# control.net
KiCad netlist of a schematic drawn in Altium Designer
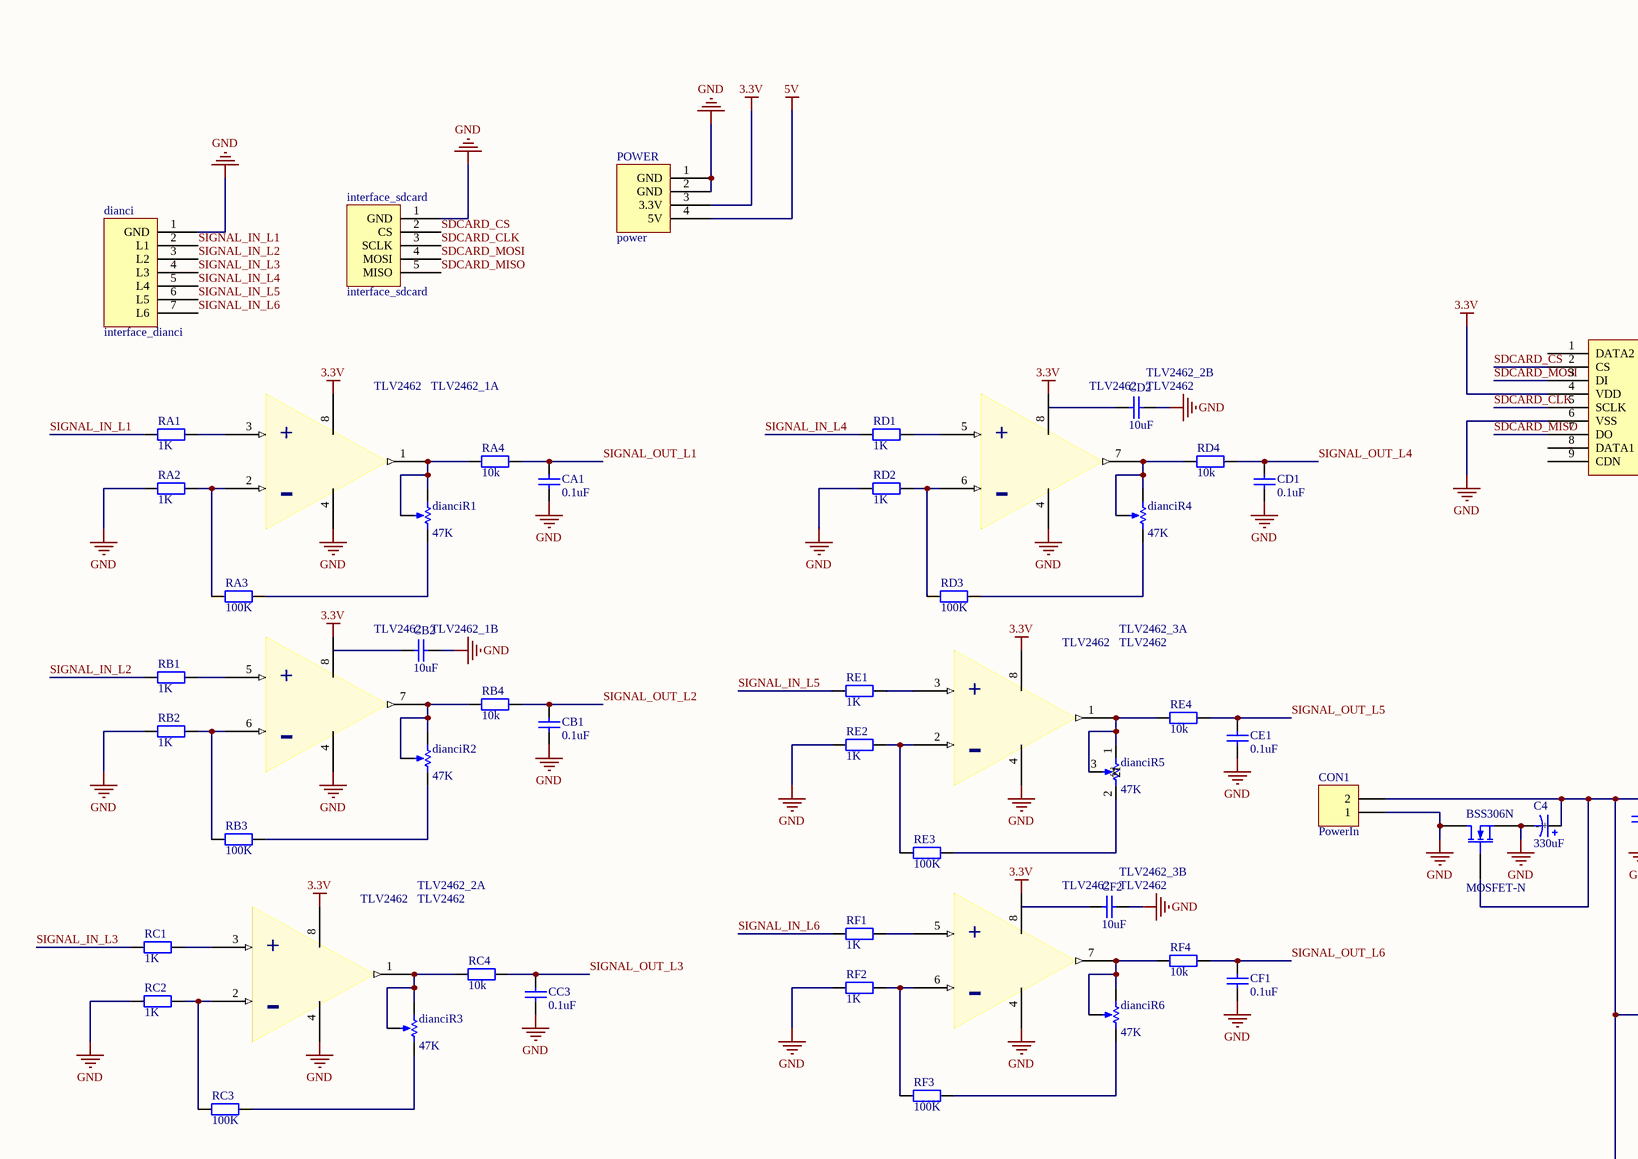
[diagram p0: control.SchDoc, top left]
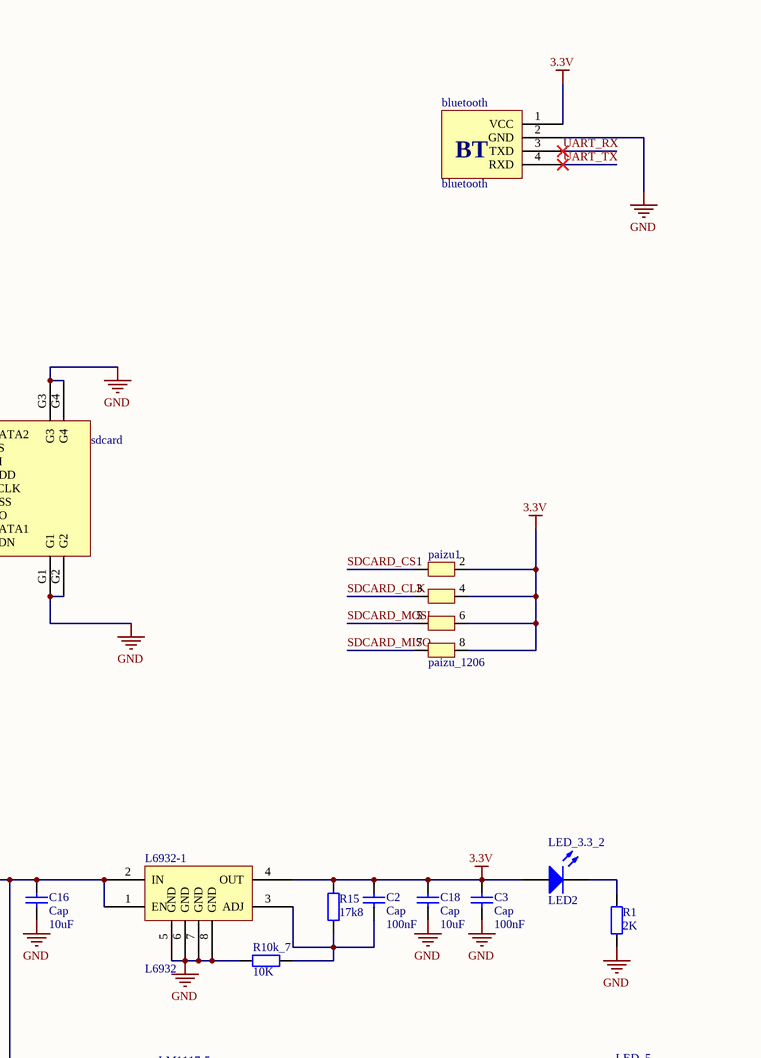
[diagram p1: control.SchDoc, top right]
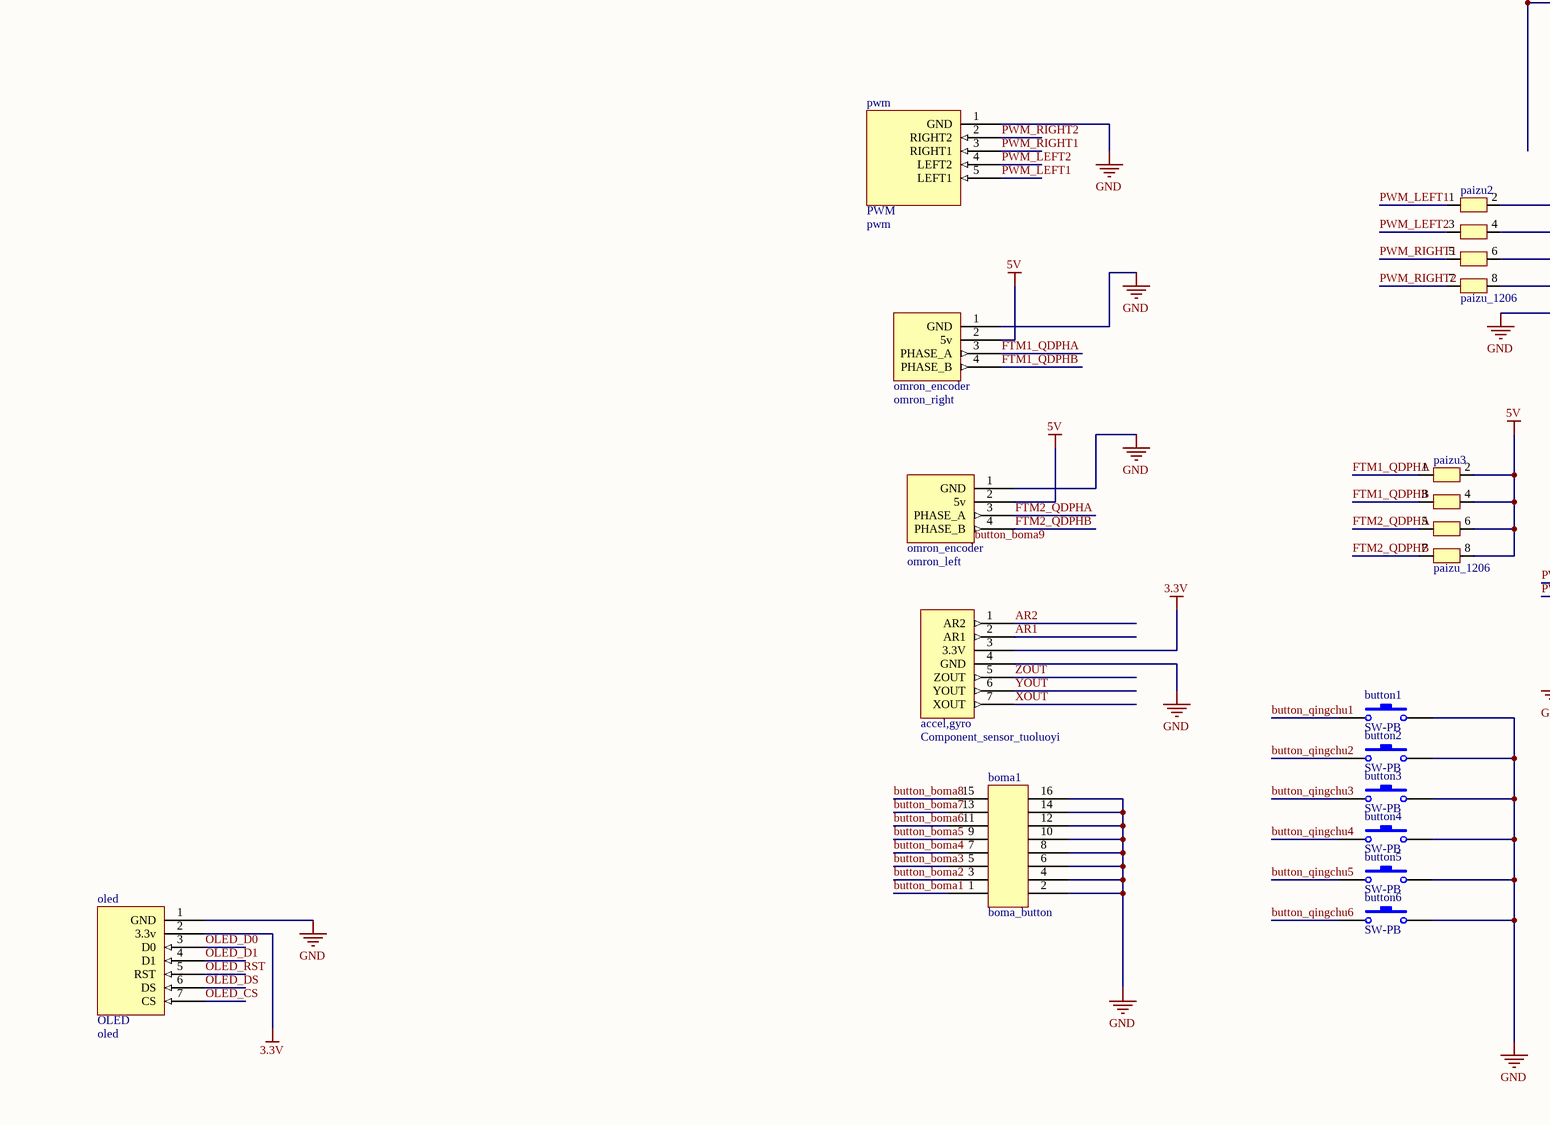
[diagram p2: control.SchDoc, bottom left]
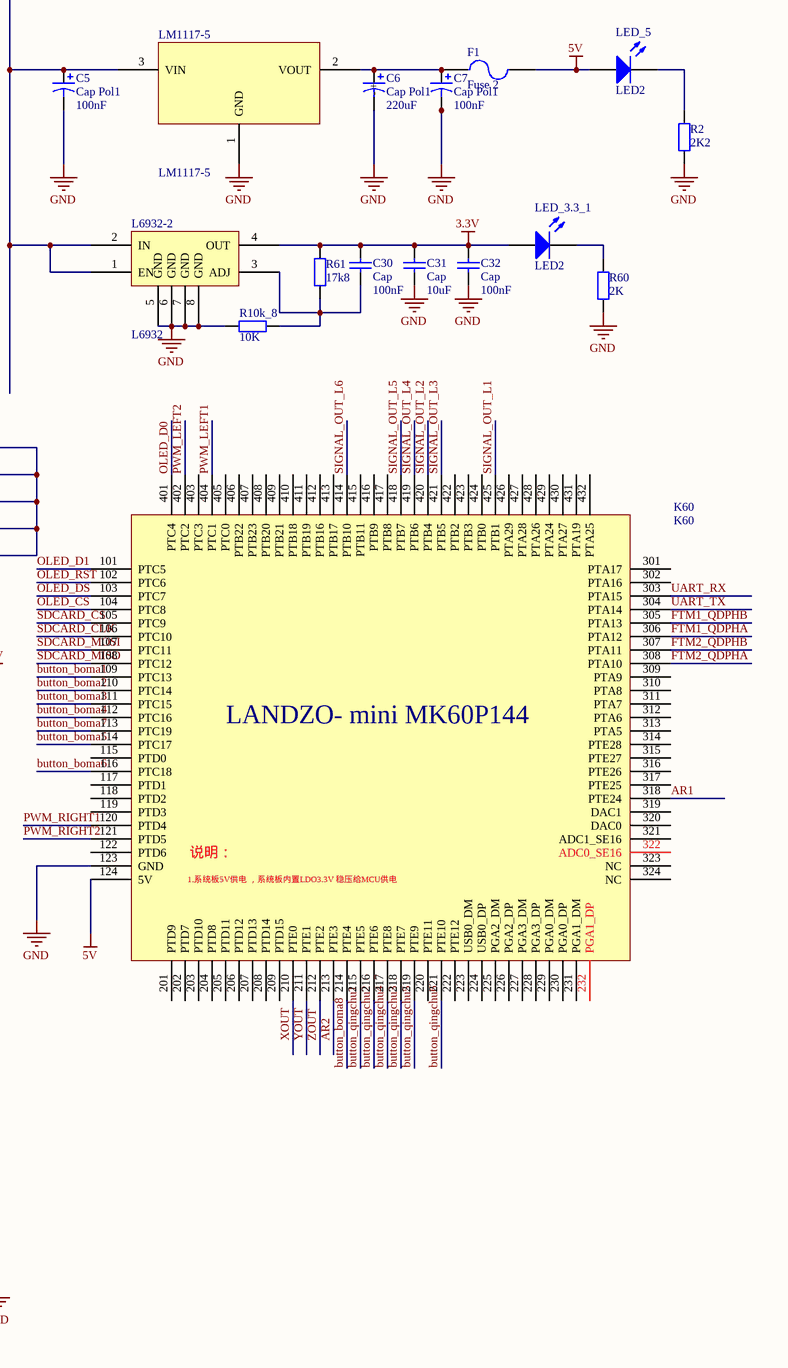
[diagram p3: control.SchDoc, bottom right]

(export (version "E")
  (design (tool "Eeschema 10.0.6"))
  (components
    (comp (ref "bluetooth")
      (value "bluetooth")
      (footprint "HDR1X4")
      (libsource (lib "PCB_Project1") (part "bluetooth"))
    )
    (comp (ref "boma1")
      (value "boma_button")
      (footprint "config_8")
      (libsource (lib "Schlib_k60_core") (part "boma_button"))
    )
    (comp (ref "BSS306N")
      (value "MOSFET-N")
      (footprint "SOT-23_M")
      (description "N-Channel MOSFET")
      (fields (field (name "PUBLISHER") "Altium Limited"))
      (libsource (lib "Miscellaneous Devices") (part "MOSFET-N"))
    )
    (comp (ref "button1")
      (value "SW-PB")
      (footprint "button")
      (description "Switch")
      (fields (field (name "PUBLISHER") "Altium Limited"))
      (libsource (lib "Miscellaneous Devices") (part "SW-PB"))
    )
    (comp (ref "button2")
      (value "SW-PB")
      (footprint "button")
      (description "Switch")
      (fields (field (name "PUBLISHER") "Altium Limited"))
      (libsource (lib "Miscellaneous Devices") (part "SW-PB"))
    )
    (comp (ref "button3")
      (value "SW-PB")
      (footprint "button")
      (description "Switch")
      (fields (field (name "PUBLISHER") "Altium Limited"))
      (libsource (lib "Miscellaneous Devices") (part "SW-PB"))
    )
    (comp (ref "button4")
      (value "SW-PB")
      (footprint "button")
      (description "Switch")
      (fields (field (name "PUBLISHER") "Altium Limited"))
      (libsource (lib "Miscellaneous Devices") (part "SW-PB"))
    )
    (comp (ref "button5")
      (value "SW-PB")
      (footprint "button")
      (description "Switch")
      (fields (field (name "PUBLISHER") "Altium Limited"))
      (libsource (lib "Miscellaneous Devices") (part "SW-PB"))
    )
    (comp (ref "button6")
      (value "SW-PB")
      (footprint "button")
      (description "Switch")
      (fields (field (name "PUBLISHER") "Altium Limited"))
      (libsource (lib "Miscellaneous Devices") (part "SW-PB"))
    )
    (comp (ref "C2")
      (value "Cap")
      (footprint "0805")
      (description "Capacitor")
      (fields (field (name "ALTIUM_VALUE") "100nF") (field (name "PUBLISHER") "Altium Limited"))
      (libsource (lib "Miscellaneous Devices") (part "Cap"))
    )
    (comp (ref "C3")
      (value "Cap")
      (footprint "0805")
      (description "Capacitor")
      (fields (field (name "ALTIUM_VALUE") "100nF") (field (name "PUBLISHER") "Altium Limited"))
      (libsource (lib "Miscellaneous Devices") (part "Cap"))
    )
    (comp (ref "C4")
      (value "330uF")
      (footprint "RB5-10.5")
      (description "Polarized Capacitor (Radial)")
      (fields (field (name "Comment") "Cap Pol1") (field (name "PUBLISHER") "Altium Limited"))
      (libsource (lib "Miscellaneous Devices") (part "Cap Pol1"))
    )
    (comp (ref "C5")
      (value "Cap Pol1")
      (footprint "钽电容_小")
      (description "Polarized Capacitor (Radial)")
      (fields (field (name "ALTIUM_VALUE") "100nF") (field (name "PUBLISHER") "Altium Limited"))
      (libsource (lib "") (part "Cap Pol1_1"))
    )
    (comp (ref "C6")
      (value "Cap Pol1")
      (footprint "D7343")
      (description "Polarized Capacitor (Radial)")
      (fields (field (name "ALTIUM_VALUE") "220uF") (field (name "PUBLISHER") "Altium Limited"))
      (libsource (lib "Miscellaneous Devices") (part "Cap Pol1"))
    )
    (comp (ref "C7")
      (value "Cap Pol1")
      (footprint "钽电容_小")
      (description "Polarized Capacitor (Radial)")
      (fields (field (name "ALTIUM_VALUE") "100nF") (field (name "PUBLISHER") "Altium Limited"))
      (libsource (lib "") (part "Cap Pol1_1"))
    )
    (comp (ref "C16")
      (value "Cap")
      (footprint "0805")
      (description "Capacitor")
      (fields (field (name "ALTIUM_VALUE") "10uF") (field (name "PUBLISHER") "Altium Limited"))
      (libsource (lib "Miscellaneous Devices") (part "Cap"))
    )
    (comp (ref "C18")
      (value "Cap")
      (footprint "0805")
      (description "Capacitor")
      (fields (field (name "ALTIUM_VALUE") "10uF") (field (name "PUBLISHER") "Altium Limited"))
      (libsource (lib "Miscellaneous Devices") (part "Cap"))
    )
    (comp (ref "C30")
      (value "Cap")
      (footprint "0805")
      (description "Capacitor")
      (fields (field (name "ALTIUM_VALUE") "100nF") (field (name "PUBLISHER") "Altium Limited"))
      (libsource (lib "Miscellaneous Devices") (part "Cap"))
    )
    (comp (ref "C31")
      (value "Cap")
      (footprint "0805")
      (description "Capacitor")
      (fields (field (name "ALTIUM_VALUE") "10uF") (field (name "PUBLISHER") "Altium Limited"))
      (libsource (lib "Miscellaneous Devices") (part "Cap"))
    )
    (comp (ref "C32")
      (value "Cap")
      (footprint "0805")
      (description "Capacitor")
      (fields (field (name "ALTIUM_VALUE") "100nF") (field (name "PUBLISHER") "Altium Limited"))
      (libsource (lib "Miscellaneous Devices") (part "Cap"))
    )
    (comp (ref "CA1")
      (value "0.1uF")
      (footprint "0805")
      (description "Capacitor")
      (fields (field (name "Comment") "Cap") (field (name "PUBLISHER") "Altium Limited"))
      (libsource (lib "Miscellaneous Devices") (part "Cap"))
    )
    (comp (ref "CB1")
      (value "0.1uF")
      (footprint "0805")
      (description "Capacitor")
      (fields (field (name "Comment") "Cap") (field (name "PUBLISHER") "Altium Limited"))
      (libsource (lib "Miscellaneous Devices") (part "Cap"))
    )
    (comp (ref "CB2")
      (value "10uF")
      (footprint "0805")
      (description "Capacitor")
      (fields (field (name "Comment") "Cap") (field (name "PUBLISHER") "Altium Limited"))
      (libsource (lib "Miscellaneous Devices") (part "Cap"))
    )
    (comp (ref "CC3")
      (value "0.1uF")
      (footprint "0805")
      (description "Capacitor")
      (fields (field (name "Comment") "Cap") (field (name "PUBLISHER") "Altium Limited"))
      (libsource (lib "Miscellaneous Devices") (part "Cap"))
    )
    (comp (ref "CD1")
      (value "0.1uF")
      (footprint "0805")
      (description "Capacitor")
      (fields (field (name "Comment") "Cap") (field (name "PUBLISHER") "Altium Limited"))
      (libsource (lib "Miscellaneous Devices") (part "Cap"))
    )
    (comp (ref "CD2")
      (value "10uF")
      (footprint "0805")
      (description "Capacitor")
      (fields (field (name "Comment") "Cap") (field (name "PUBLISHER") "Altium Limited"))
      (libsource (lib "Miscellaneous Devices") (part "Cap"))
    )
    (comp (ref "CE1")
      (value "0.1uF")
      (footprint "0805")
      (description "Capacitor")
      (fields (field (name "Comment") "Cap") (field (name "PUBLISHER") "Altium Limited"))
      (libsource (lib "Miscellaneous Devices") (part "Cap"))
    )
    (comp (ref "CF1")
      (value "0.1uF")
      (footprint "0805")
      (description "Capacitor")
      (fields (field (name "Comment") "Cap") (field (name "PUBLISHER") "Altium Limited"))
      (libsource (lib "Miscellaneous Devices") (part "Cap"))
    )
    (comp (ref "CF2")
      (value "10uF")
      (footprint "0805")
      (description "Capacitor")
      (fields (field (name "Comment") "Cap") (field (name "PUBLISHER") "Altium Limited"))
      (libsource (lib "Miscellaneous Devices") (part "Cap"))
    )
    (comp (ref "CON1")
      (value "PowerIn")
      (footprint "接线端子")
      (description "Header, 2-Pin")
      (fields (field (name "PUBLISHER") "Altium Limited"))
      (libsource (lib "Miscellaneous Connectors") (part "Header 2"))
    )
    (comp (ref "dianci")
      (value "interface_dianci")
      (footprint "HDR1X7H")
      (libsource (lib "Schlib_k60_core") (part "interface_dianci"))
    )
    (comp (ref "dianciR1")
      (value "47K")
      (footprint "滑动变阻器")
      (description "Potentiometer")
      (fields (field (name "Comment") "R4") (field (name "PUBLISHER") "Altium Limited"))
      (libsource (lib "") (part "RPot_1"))
    )
    (comp (ref "dianciR2")
      (value "47K")
      (footprint "滑动变阻器")
      (description "Potentiometer")
      (fields (field (name "Comment") "R4") (field (name "PUBLISHER") "Altium Limited"))
      (libsource (lib "") (part "RPot_1"))
    )
    (comp (ref "dianciR3")
      (value "47K")
      (footprint "滑动变阻器")
      (description "Potentiometer")
      (fields (field (name "Comment") "R4") (field (name "PUBLISHER") "Altium Limited"))
      (libsource (lib "") (part "RPot_1"))
    )
    (comp (ref "dianciR4")
      (value "47K")
      (footprint "滑动变阻器")
      (description "Potentiometer")
      (fields (field (name "Comment") "R4") (field (name "PUBLISHER") "Altium Limited"))
      (libsource (lib "") (part "RPot_1"))
    )
    (comp (ref "dianciR5")
      (value "47K")
      (footprint "滑动变阻器")
      (description "Potentiometer")
      (fields (field (name "Comment") "R4") (field (name "PUBLISHER") "Altium Limited"))
      (libsource (lib "Miscellaneous Devices") (part "RPot"))
    )
    (comp (ref "dianciR6")
      (value "47K")
      (footprint "滑动变阻器")
      (description "Potentiometer")
      (fields (field (name "Comment") "R4") (field (name "PUBLISHER") "Altium Limited"))
      (libsource (lib "") (part "RPot_1"))
    )
    (comp (ref "F1")
      (value "Fuse 2")
      (footprint "0805")
      (description "Fuse")
      (fields (field (name "PUBLISHER") "Altium Limited"))
      (libsource (lib "Miscellaneous Devices") (part "Fuse 2"))
    )
    (comp (ref "interface_sdcard")
      (value "interface_sdcard")
      (footprint "HDR1X5H")
      (libsource (lib "Schlib_k60_core") (part "interface_sdcard"))
    )
    (comp (ref "K60")
      (value "K60")
      (footprint "K60 V4.0最小系统版")
      (libsource (lib "K60P144 V5.1") (part "Component_1"))
    )
    (comp (ref "L6932-1")
      (value "L6932")
      (footprint "L6932")
      (libsource (lib "Schlib_k60_core") (part "L6932"))
    )
    (comp (ref "L6932-2")
      (value "L6932")
      (footprint "L6932")
      (libsource (lib "Schlib_k60_core") (part "L6932"))
    )
    (comp (ref "LED_3.3_1")
      (value "LED2")
      (footprint "0805")
      (description "Typical RED, GREEN, YELLOW, AMBER GaAs LED")
      (fields (field (name "PUBLISHER") "Altium Limited"))
      (libsource (lib "Miscellaneous Devices") (part "LED2"))
    )
    (comp (ref "LED_3.3_2")
      (value "LED2")
      (footprint "0805")
      (description "Typical RED, GREEN, YELLOW, AMBER GaAs LED")
      (fields (field (name "PUBLISHER") "Altium Limited"))
      (libsource (lib "Miscellaneous Devices") (part "LED2"))
    )
    (comp (ref "LED_5")
      (value "LED2")
      (footprint "0805")
      (description "Typical RED, GREEN, YELLOW, AMBER GaAs LED")
      (fields (field (name "PUBLISHER") "Altium Limited"))
      (libsource (lib "Miscellaneous Devices") (part "LED2"))
    )
    (comp (ref "LM1117-5")
      (value "LM1117-5")
      (footprint "SOT223_M")
      (libsource (lib "Schlib_k60_core") (part "LM1117-5"))
    )
    (comp (ref "oled") (value "oled") (footprint "HDR1X7H") (libsource (lib "Schlib_k60_core") (part "oled")))
    (comp (ref "omron_left")
      (value "omron_encoder")
      (footprint "HDR1X4H")
      (libsource (lib "Schlib_k60_core") (part "omron_encoder"))
    )
    (comp (ref "omron_right")
      (value "omron_encoder")
      (footprint "HDR1X4H")
      (libsource (lib "Schlib_k60_core") (part "omron_encoder"))
    )
    (comp (ref "paizu1")
      (value "paizu_1206")
      (footprint "paizu")
      (libsource (lib "Schlib_k60_core") (part "paizu_1206"))
    )
    (comp (ref "paizu2")
      (value "paizu_1206")
      (footprint "paizu")
      (libsource (lib "Schlib_k60_core") (part "paizu_1206"))
    )
    (comp (ref "paizu3")
      (value "paizu_1206")
      (footprint "paizu")
      (libsource (lib "Schlib_k60_core") (part "paizu_1206"))
    )
    (comp (ref "POWER")
      (value "power")
      (footprint "HDR1X4H")
      (libsource (lib "Schlib_k60_core") (part "power"))
    )
    (comp (ref "pwm") (value "pwm") (footprint "HDR1X5H") (libsource (lib "Schlib_k60_core") (part "pwm")))
    (comp (ref "R1")
      (value "2K")
      (footprint "0805")
      (description "Resistor")
      (fields (field (name "Comment") "Res2") (field (name "PUBLISHER") "Altium Limited"))
      (libsource (lib "Miscellaneous Devices") (part "Res2"))
    )
    (comp (ref "R2")
      (value "2K2")
      (footprint "0805")
      (description "Resistor")
      (fields (field (name "Comment") "Res2") (field (name "PUBLISHER") "Altium Limited"))
      (libsource (lib "Miscellaneous Devices") (part "Res2"))
    )
    (comp (ref "R10k_7")
      (value "10K")
      (footprint "0805")
      (description "Resistor")
      (fields (field (name "Comment") "Res2") (field (name "PUBLISHER") "Altium Limited"))
      (libsource (lib "") (part "Res2_1"))
    )
    (comp (ref "R10k_8")
      (value "10K")
      (footprint "0805")
      (description "Resistor")
      (fields (field (name "Comment") "Res2") (field (name "PUBLISHER") "Altium Limited"))
      (libsource (lib "") (part "Res2_1"))
    )
    (comp (ref "R15")
      (value "17k8")
      (footprint "0805")
      (description "Resistor")
      (fields (field (name "Comment") "Res2") (field (name "PUBLISHER") "Altium Limited"))
      (libsource (lib "Miscellaneous Devices") (part "Res2"))
    )
    (comp (ref "R60")
      (value "2K")
      (footprint "0805")
      (description "Resistor")
      (fields (field (name "Comment") "Res2") (field (name "PUBLISHER") "Altium Limited"))
      (libsource (lib "Miscellaneous Devices") (part "Res2"))
    )
    (comp (ref "R61")
      (value "17k8")
      (footprint "0805")
      (description "Resistor")
      (fields (field (name "Comment") "Res2") (field (name "PUBLISHER") "Altium Limited"))
      (libsource (lib "Miscellaneous Devices") (part "Res2"))
    )
    (comp (ref "RA1")
      (value "1K")
      (footprint "0805")
      (description "Resistor")
      (fields (field (name "Comment") "Res2") (field (name "PUBLISHER") "Altium Limited"))
      (libsource (lib "") (part "Res2_1"))
    )
    (comp (ref "RA2")
      (value "1K")
      (footprint "0805")
      (description "Resistor")
      (fields (field (name "Comment") "Res2") (field (name "PUBLISHER") "Altium Limited"))
      (libsource (lib "") (part "Res2_1"))
    )
    (comp (ref "RA3")
      (value "100K")
      (footprint "0805")
      (description "Resistor")
      (fields (field (name "Comment") "Res2") (field (name "PUBLISHER") "Altium Limited"))
      (libsource (lib "") (part "Res2_1"))
    )
    (comp (ref "RA4")
      (value "10k")
      (footprint "0805")
      (description "Resistor")
      (fields (field (name "Comment") "Res2") (field (name "PUBLISHER") "Altium Limited"))
      (libsource (lib "") (part "Res2_1"))
    )
    (comp (ref "RB1")
      (value "1K")
      (footprint "0805")
      (description "Resistor")
      (fields (field (name "Comment") "Res2") (field (name "PUBLISHER") "Altium Limited"))
      (libsource (lib "") (part "Res2_1"))
    )
    (comp (ref "RB2")
      (value "1K")
      (footprint "0805")
      (description "Resistor")
      (fields (field (name "Comment") "Res2") (field (name "PUBLISHER") "Altium Limited"))
      (libsource (lib "") (part "Res2_1"))
    )
    (comp (ref "RB3")
      (value "100K")
      (footprint "0805")
      (description "Resistor")
      (fields (field (name "Comment") "Res2") (field (name "PUBLISHER") "Altium Limited"))
      (libsource (lib "") (part "Res2_1"))
    )
    (comp (ref "RB4")
      (value "10k")
      (footprint "0805")
      (description "Resistor")
      (fields (field (name "Comment") "Res2") (field (name "PUBLISHER") "Altium Limited"))
      (libsource (lib "") (part "Res2_1"))
    )
    (comp (ref "RC1")
      (value "1K")
      (footprint "0805")
      (description "Resistor")
      (fields (field (name "Comment") "Res2") (field (name "PUBLISHER") "Altium Limited"))
      (libsource (lib "") (part "Res2_1"))
    )
    (comp (ref "RC2")
      (value "1K")
      (footprint "0805")
      (description "Resistor")
      (fields (field (name "Comment") "Res2") (field (name "PUBLISHER") "Altium Limited"))
      (libsource (lib "") (part "Res2_1"))
    )
    (comp (ref "RC3")
      (value "100K")
      (footprint "0805")
      (description "Resistor")
      (fields (field (name "Comment") "Res2") (field (name "PUBLISHER") "Altium Limited"))
      (libsource (lib "") (part "Res2_1"))
    )
    (comp (ref "RC4")
      (value "10k")
      (footprint "0805")
      (description "Resistor")
      (fields (field (name "Comment") "Res2") (field (name "PUBLISHER") "Altium Limited"))
      (libsource (lib "") (part "Res2_1"))
    )
    (comp (ref "RD1")
      (value "1K")
      (footprint "0805")
      (description "Resistor")
      (fields (field (name "Comment") "Res2") (field (name "PUBLISHER") "Altium Limited"))
      (libsource (lib "") (part "Res2_1"))
    )
    (comp (ref "RD2")
      (value "1K")
      (footprint "0805")
      (description "Resistor")
      (fields (field (name "Comment") "Res2") (field (name "PUBLISHER") "Altium Limited"))
      (libsource (lib "") (part "Res2_1"))
    )
    (comp (ref "RD3")
      (value "100K")
      (footprint "0805")
      (description "Resistor")
      (fields (field (name "Comment") "Res2") (field (name "PUBLISHER") "Altium Limited"))
      (libsource (lib "") (part "Res2_1"))
    )
    (comp (ref "RD4")
      (value "10k")
      (footprint "0805")
      (description "Resistor")
      (fields (field (name "Comment") "Res2") (field (name "PUBLISHER") "Altium Limited"))
      (libsource (lib "") (part "Res2_1"))
    )
    (comp (ref "RE1")
      (value "1K")
      (footprint "0805")
      (description "Resistor")
      (fields (field (name "Comment") "Res2") (field (name "PUBLISHER") "Altium Limited"))
      (libsource (lib "") (part "Res2_1"))
    )
    (comp (ref "RE2")
      (value "1K")
      (footprint "0805")
      (description "Resistor")
      (fields (field (name "Comment") "Res2") (field (name "PUBLISHER") "Altium Limited"))
      (libsource (lib "") (part "Res2_1"))
    )
    (comp (ref "RE3")
      (value "100K")
      (footprint "0805")
      (description "Resistor")
      (fields (field (name "Comment") "Res2") (field (name "PUBLISHER") "Altium Limited"))
      (libsource (lib "") (part "Res2_1"))
    )
    (comp (ref "RE4")
      (value "10k")
      (footprint "0805")
      (description "Resistor")
      (fields (field (name "Comment") "Res2") (field (name "PUBLISHER") "Altium Limited"))
      (libsource (lib "") (part "Res2_1"))
    )
    (comp (ref "RF1")
      (value "1K")
      (footprint "0805")
      (description "Resistor")
      (fields (field (name "Comment") "Res2") (field (name "PUBLISHER") "Altium Limited"))
      (libsource (lib "") (part "Res2_1"))
    )
    (comp (ref "RF2")
      (value "1K")
      (footprint "0805")
      (description "Resistor")
      (fields (field (name "Comment") "Res2") (field (name "PUBLISHER") "Altium Limited"))
      (libsource (lib "") (part "Res2_1"))
    )
    (comp (ref "RF3")
      (value "100K")
      (footprint "0805")
      (description "Resistor")
      (fields (field (name "Comment") "Res2") (field (name "PUBLISHER") "Altium Limited"))
      (libsource (lib "") (part "Res2_1"))
    )
    (comp (ref "RF4")
      (value "10k")
      (footprint "0805")
      (description "Resistor")
      (fields (field (name "Comment") "Res2") (field (name "PUBLISHER") "Altium Limited"))
      (libsource (lib "") (part "Res2_1"))
    )
    (comp (ref "sdcard")
      (value "sdcard")
      (footprint "SDCARD-M")
      (libsource (lib "Schlib_k60_core") (part "sdcard"))
    )
    (comp (ref "TLV2462_1")
      (value "TLV2462")
      (footprint "SOP127P600X175-8L")
      (libsource (lib "Schlib_k60_core") (part "TLV2462"))
    )
    (comp (ref "TLV2462_2")
      (value "TLV2462")
      (footprint "SOP127P600X175-8L")
      (libsource (lib "Schlib_k60_core") (part "TLV2462"))
    )
    (comp (ref "TLV2462_3")
      (value "TLV2462")
      (footprint "SOP127P600X175-8L")
      (libsource (lib "Schlib_k60_core") (part "TLV2462"))
    )
    (comp (ref "tuoluoyi")
      (value "Component_sensor_tuoluoyi")
      (footprint "HDR1X7H")
      (libsource (lib "Schlib_k60_core") (part "Component_sensor_tuoluoyi"))
    )
  )
  (nets
    (net (code "1") (name "/AR1") (class "Default")
      (node (ref "K60") (pin "318") (pinfunction "PTE24_318") (pintype "passive"))
      (node (ref "tuoluoyi") (pin "2") (pinfunction "AR1_2") (pintype "output"))
    )
    (net (code "2") (name "/AR2") (class "Default")
      (node (ref "K60") (pin "213") (pinfunction "PTE3_213") (pintype "passive"))
      (node (ref "tuoluoyi") (pin "1") (pinfunction "AR2_1") (pintype "output"))
    )
    (net (code "3") (name "/FTM1_QDPHA") (class "Default")
      (node (ref "K60") (pin "306") (pinfunction "PTA12_306") (pintype "passive"))
      (node (ref "omron_right") (pin "3") (pinfunction "PHASE_A_3") (pintype "output"))
      (node (ref "paizu3") (pin "1") (pinfunction "1_1") (pintype "power_in"))
    )
    (net (code "4") (name "/FTM1_QDPHB") (class "Default")
      (node (ref "K60") (pin "305") (pinfunction "PTA13_305") (pintype "passive"))
      (node (ref "omron_right") (pin "4") (pinfunction "PHASE_B_4") (pintype "output"))
      (node (ref "paizu3") (pin "3") (pinfunction "3_3") (pintype "power_in"))
    )
    (net (code "5") (name "/FTM2_QDPHA") (class "Default")
      (node (ref "K60") (pin "308") (pinfunction "PTA10_308") (pintype "passive"))
      (node (ref "omron_left") (pin "3") (pinfunction "PHASE_A_3") (pintype "output"))
      (node (ref "paizu3") (pin "5") (pinfunction "5_5") (pintype "power_in"))
    )
    (net (code "6") (name "/FTM2_QDPHB") (class "Default")
      (node (ref "K60") (pin "307") (pinfunction "PTA11_307") (pintype "passive"))
      (node (ref "omron_left") (pin "4") (pinfunction "PHASE_B_4") (pintype "output"))
      (node (ref "paizu3") (pin "7") (pinfunction "7_7") (pintype "power_in"))
    )
    (net (code "7") (name "/OLED_CS") (class "Default")
      (node (ref "K60") (pin "104") (pinfunction "PTC8_104") (pintype "passive"))
      (node (ref "oled") (pin "7") (pinfunction "CS_7") (pintype "input"))
    )
    (net (code "8") (name "/OLED_D0") (class "Default")
      (node (ref "K60") (pin "401") (pinfunction "PTC4_401") (pintype "passive"))
      (node (ref "oled") (pin "3") (pinfunction "D0_3") (pintype "input"))
    )
    (net (code "9") (name "/OLED_D1") (class "Default")
      (node (ref "K60") (pin "101") (pinfunction "PTC5_101") (pintype "passive"))
      (node (ref "oled") (pin "4") (pinfunction "D1_4") (pintype "input"))
    )
    (net (code "10") (name "/OLED_DS") (class "Default")
      (node (ref "K60") (pin "103") (pinfunction "PTC7_103") (pintype "passive"))
      (node (ref "oled") (pin "6") (pinfunction "DS_6") (pintype "input"))
    )
    (net (code "11") (name "/OLED_RST") (class "Default")
      (node (ref "K60") (pin "102") (pinfunction "PTC6_102") (pintype "passive"))
      (node (ref "oled") (pin "5") (pinfunction "RST_5") (pintype "input"))
    )
    (net (code "12") (name "/PWM_LEFT1") (class "Default")
      (node (ref "K60") (pin "404") (pinfunction "PTC1_404") (pintype "passive"))
      (node (ref "paizu2") (pin "1") (pinfunction "1_1") (pintype "power_in"))
      (node (ref "pwm") (pin "5") (pinfunction "LEFT1_5") (pintype "input"))
    )
    (net (code "13") (name "/PWM_LEFT2") (class "Default")
      (node (ref "K60") (pin "402") (pinfunction "PTC2_402") (pintype "passive"))
      (node (ref "paizu2") (pin "3") (pinfunction "3_3") (pintype "power_in"))
      (node (ref "pwm") (pin "4") (pinfunction "LEFT2_4") (pintype "input"))
    )
    (net (code "14") (name "/PWM_RIGHT1") (class "Default")
      (node (ref "K60") (pin "120") (pinfunction "PTD4_120") (pintype "passive"))
      (node (ref "paizu2") (pin "5") (pinfunction "5_5") (pintype "power_in"))
      (node (ref "pwm") (pin "3") (pinfunction "RIGHT1_3") (pintype "input"))
    )
    (net (code "15") (name "/PWM_RIGHT2") (class "Default")
      (node (ref "K60") (pin "121") (pinfunction "PTD5_121") (pintype "passive"))
      (node (ref "paizu2") (pin "7") (pinfunction "7_7") (pintype "power_in"))
      (node (ref "pwm") (pin "2") (pinfunction "RIGHT2_2") (pintype "input"))
    )
    (net (code "16") (name "/SDCARD_CLK") (class "Default")
      (node (ref "K60") (pin "106") (pinfunction "PTC10_106") (pintype "passive"))
      (node (ref "interface_sdcard") (pin "3") (pinfunction "SCLK_3") (pintype "power_in"))
      (node (ref "paizu1") (pin "3") (pinfunction "3_3") (pintype "power_in"))
      (node (ref "sdcard") (pin "5") (pinfunction "SCLK_5") (pintype "power_in"))
    )
    (net (code "17") (name "/SDCARD_CS") (class "Default")
      (node (ref "K60") (pin "105") (pinfunction "PTC9_105") (pintype "passive"))
      (node (ref "interface_sdcard") (pin "2") (pinfunction "CS_2") (pintype "power_in"))
      (node (ref "paizu1") (pin "1") (pinfunction "1_1") (pintype "power_in"))
      (node (ref "sdcard") (pin "2") (pinfunction "CS_2") (pintype "power_in"))
    )
    (net (code "18") (name "/SDCARD_MISO") (class "Default")
      (node (ref "K60") (pin "108") (pinfunction "PTC12_108") (pintype "passive"))
      (node (ref "interface_sdcard") (pin "5") (pinfunction "MISO_5") (pintype "power_in"))
      (node (ref "paizu1") (pin "7") (pinfunction "7_7") (pintype "power_in"))
      (node (ref "sdcard") (pin "7") (pinfunction "DO_7") (pintype "power_in"))
    )
    (net (code "19") (name "/SDCARD_MOSI") (class "Default")
      (node (ref "K60") (pin "107") (pinfunction "PTC11_107") (pintype "passive"))
      (node (ref "interface_sdcard") (pin "4") (pinfunction "MOSI_4") (pintype "power_in"))
      (node (ref "paizu1") (pin "5") (pinfunction "5_5") (pintype "power_in"))
      (node (ref "sdcard") (pin "3") (pinfunction "DI_3") (pintype "power_in"))
    )
    (net (code "20") (name "/SIGNAL_IN_L1") (class "Default")
      (node (ref "RA1") (pin "1") (pinfunction "1_1") (pintype "passive"))
      (node (ref "dianci") (pin "2") (pinfunction "L1_2") (pintype "power_in"))
    )
    (net (code "21") (name "/SIGNAL_IN_L2") (class "Default")
      (node (ref "RB1") (pin "1") (pinfunction "1_1") (pintype "passive"))
      (node (ref "dianci") (pin "3") (pinfunction "L2_3") (pintype "power_in"))
    )
    (net (code "22") (name "/SIGNAL_IN_L3") (class "Default")
      (node (ref "RC1") (pin "1") (pinfunction "1_1") (pintype "passive"))
      (node (ref "dianci") (pin "4") (pinfunction "L3_4") (pintype "power_in"))
    )
    (net (code "23") (name "/SIGNAL_IN_L4") (class "Default")
      (node (ref "RD1") (pin "1") (pinfunction "1_1") (pintype "passive"))
      (node (ref "dianci") (pin "5") (pinfunction "L4_5") (pintype "power_in"))
    )
    (net (code "24") (name "/SIGNAL_IN_L5") (class "Default")
      (node (ref "RE1") (pin "1") (pinfunction "1_1") (pintype "passive"))
      (node (ref "dianci") (pin "6") (pinfunction "L5_6") (pintype "power_in"))
    )
    (net (code "25") (name "/SIGNAL_IN_L6") (class "Default")
      (node (ref "RF1") (pin "1") (pinfunction "1_1") (pintype "passive"))
      (node (ref "dianci") (pin "7") (pinfunction "L6_7") (pintype "power_in"))
    )
    (net (code "26") (name "/SIGNAL_OUT_L1") (class "Default")
      (node (ref "CA1") (pin "2") (pinfunction "2_2") (pintype "passive"))
      (node (ref "K60") (pin "425") (pinfunction "PTB1_425") (pintype "passive"))
      (node (ref "RA4") (pin "2") (pinfunction "2_2") (pintype "passive"))
    )
    (net (code "27") (name "/SIGNAL_OUT_L2") (class "Default")
      (node (ref "CB1") (pin "2") (pinfunction "2_2") (pintype "passive"))
      (node (ref "K60") (pin "420") (pinfunction "PTB4_420") (pintype "passive"))
      (node (ref "RB4") (pin "2") (pinfunction "2_2") (pintype "passive"))
    )
    (net (code "28") (name "/SIGNAL_OUT_L3") (class "Default")
      (node (ref "CC3") (pin "2") (pinfunction "2_2") (pintype "passive"))
      (node (ref "K60") (pin "421") (pinfunction "PTB5_421") (pintype "passive"))
      (node (ref "RC4") (pin "2") (pinfunction "2_2") (pintype "passive"))
    )
    (net (code "29") (name "/SIGNAL_OUT_L4") (class "Default")
      (node (ref "CD1") (pin "2") (pinfunction "2_2") (pintype "passive"))
      (node (ref "K60") (pin "419") (pinfunction "PTB6_419") (pintype "passive"))
      (node (ref "RD4") (pin "2") (pinfunction "2_2") (pintype "passive"))
    )
    (net (code "30") (name "/SIGNAL_OUT_L5") (class "Default")
      (node (ref "CE1") (pin "2") (pinfunction "2_2") (pintype "passive"))
      (node (ref "K60") (pin "418") (pinfunction "PTB7_418") (pintype "passive"))
      (node (ref "RE4") (pin "2") (pinfunction "2_2") (pintype "passive"))
    )
    (net (code "31") (name "/SIGNAL_OUT_L6") (class "Default")
      (node (ref "CF1") (pin "2") (pinfunction "2_2") (pintype "passive"))
      (node (ref "K60") (pin "414") (pinfunction "PTB10_414") (pintype "passive"))
      (node (ref "RF4") (pin "2") (pinfunction "2_2") (pintype "passive"))
    )
    (net (code "32") (name "/UART_RX") (class "Default")
      (node (ref "K60") (pin "303") (pinfunction "PTA15_303") (pintype "passive"))
      (node (ref "bluetooth") (pin "3") (pinfunction "TXD_3") (pintype "power_in"))
    )
    (net (code "33") (name "/UART_TX") (class "Default")
      (node (ref "K60") (pin "304") (pinfunction "PTA14_304") (pintype "passive"))
      (node (ref "bluetooth") (pin "4") (pinfunction "RXD_4") (pintype "power_in"))
    )
    (net (code "34") (name "/XOUT") (class "Default")
      (node (ref "K60") (pin "210") (pinfunction "PTE0_210") (pintype "passive"))
      (node (ref "tuoluoyi") (pin "7") (pinfunction "XOUT_7") (pintype "output"))
    )
    (net (code "35") (name "/YOUT") (class "Default")
      (node (ref "K60") (pin "211") (pinfunction "PTE1_211") (pintype "passive"))
      (node (ref "tuoluoyi") (pin "6") (pinfunction "YOUT_6") (pintype "output"))
    )
    (net (code "36") (name "/ZOUT") (class "Default")
      (node (ref "K60") (pin "212") (pinfunction "PTE2_212") (pintype "passive"))
      (node (ref "tuoluoyi") (pin "5") (pinfunction "ZOUT_5") (pintype "output"))
    )
    (net (code "37") (name "/button_boma1") (class "Default")
      (node (ref "K60") (pin "109") (pinfunction "PTC13_109") (pintype "passive"))
      (node (ref "boma1") (pin "1") (pinfunction "1_1") (pintype "power_in"))
    )
    (net (code "38") (name "/button_boma2") (class "Default")
      (node (ref "K60") (pin "110") (pinfunction "PTC14_110") (pintype "passive"))
      (node (ref "boma1") (pin "3") (pinfunction "3_3") (pintype "power_in"))
    )
    (net (code "39") (name "/button_boma3") (class "Default")
      (node (ref "K60") (pin "111") (pinfunction "PTC15_111") (pintype "passive"))
      (node (ref "boma1") (pin "5") (pinfunction "5_5") (pintype "power_in"))
    )
    (net (code "40") (name "/button_boma4") (class "Default")
      (node (ref "K60") (pin "112") (pinfunction "PTC16_112") (pintype "passive"))
      (node (ref "boma1") (pin "7") (pinfunction "7_7") (pintype "power_in"))
    )
    (net (code "41") (name "/button_boma5") (class "Default")
      (node (ref "K60") (pin "114") (pinfunction "PTC17_114") (pintype "passive"))
      (node (ref "boma1") (pin "9") (pinfunction "9_9") (pintype "power_in"))
    )
    (net (code "42") (name "/button_boma6") (class "Default")
      (node (ref "K60") (pin "116") (pinfunction "PTC18_116") (pintype "passive"))
      (node (ref "boma1") (pin "11") (pinfunction "11_11") (pintype "power_in"))
    )
    (net (code "43") (name "/button_boma7") (class "Default")
      (node (ref "K60") (pin "113") (pinfunction "PTC19_113") (pintype "passive"))
      (node (ref "boma1") (pin "13") (pinfunction "13_13") (pintype "power_in"))
    )
    (net (code "44") (name "/button_boma8") (class "Default")
      (node (ref "K60") (pin "214") (pinfunction "PTE4_214") (pintype "passive"))
      (node (ref "boma1") (pin "15") (pinfunction "15_15") (pintype "power_in"))
    )
    (net (code "46") (name "/button_qingchu1") (class "Default")
      (node (ref "K60") (pin "215") (pinfunction "PTE5_215") (pintype "passive"))
      (node (ref "button1") (pin "1") (pinfunction "1_1") (pintype "passive"))
    )
    (net (code "47") (name "/button_qingchu2") (class "Default")
      (node (ref "K60") (pin "216") (pinfunction "PTE6_216") (pintype "passive"))
      (node (ref "button2") (pin "1") (pinfunction "1_1") (pintype "passive"))
    )
    (net (code "48") (name "/button_qingchu3") (class "Default")
      (node (ref "K60") (pin "218") (pinfunction "PTE7_218") (pintype "passive"))
      (node (ref "button3") (pin "1") (pinfunction "1_1") (pintype "passive"))
    )
    (net (code "49") (name "/button_qingchu4") (class "Default")
      (node (ref "K60") (pin "217") (pinfunction "PTE8_217") (pintype "passive"))
      (node (ref "button4") (pin "1") (pinfunction "1_1") (pintype "passive"))
    )
    (net (code "50") (name "/button_qingchu5") (class "Default")
      (node (ref "K60") (pin "219") (pinfunction "PTE9_219") (pintype "passive"))
      (node (ref "button5") (pin "1") (pinfunction "1_1") (pintype "passive"))
    )
    (net (code "51") (name "/button_qingchu6") (class "Default")
      (node (ref "K60") (pin "221") (pinfunction "PTE10_221") (pintype "passive"))
      (node (ref "button6") (pin "1") (pinfunction "1_1") (pintype "passive"))
    )
    (net (code "52") (name "3.3V") (class "Default")
      (node (ref "C18") (pin "2") (pinfunction "2_2") (pintype "passive"))
      (node (ref "C2") (pin "2") (pinfunction "2_2") (pintype "passive"))
      (node (ref "C3") (pin "2") (pinfunction "2_2") (pintype "passive"))
      (node (ref "C30") (pin "2") (pinfunction "2_2") (pintype "passive"))
      (node (ref "C31") (pin "2") (pinfunction "2_2") (pintype "passive"))
      (node (ref "C32") (pin "2") (pinfunction "2_2") (pintype "passive"))
      (node (ref "L6932-1") (pin "4") (pinfunction "OUT_4") (pintype "power_in"))
      (node (ref "L6932-2") (pin "4") (pinfunction "OUT_4") (pintype "power_in"))
      (node (ref "LED_3.3_1") (pin "1") (pinfunction "A_1") (pintype "passive"))
      (node (ref "LED_3.3_2") (pin "1") (pinfunction "A_1") (pintype "passive"))
      (node (ref "POWER") (pin "3") (pinfunction "3.3V_3") (pintype "power_in"))
      (node (ref "R15") (pin "2") (pinfunction "2_2") (pintype "passive"))
      (node (ref "R61") (pin "2") (pinfunction "2_2") (pintype "passive"))
      (node (ref "TLV2462_1") (pin "8") (pinfunction "VCC_8") (pintype "power_in"))
      (node (ref "TLV2462_2") (pin "8") (pinfunction "VCC_8") (pintype "power_in"))
      (node (ref "TLV2462_3") (pin "8") (pinfunction "VCC_8") (pintype "power_in"))
      (node (ref "bluetooth") (pin "1") (pinfunction "VCC_1") (pintype "power_in"))
      (node (ref "oled") (pin "2") (pinfunction "3.3v_2") (pintype "power_in"))
      (node (ref "paizu1") (pin "2") (pinfunction "2_2") (pintype "power_in"))
      (node (ref "paizu1") (pin "4") (pinfunction "4_4") (pintype "power_in"))
      (node (ref "paizu1") (pin "6") (pinfunction "6_6") (pintype "power_in"))
      (node (ref "paizu1") (pin "8") (pinfunction "8_8") (pintype "power_in"))
      (node (ref "sdcard") (pin "4") (pinfunction "VDD_4") (pintype "power_in"))
      (node (ref "tuoluoyi") (pin "3") (pinfunction "3.3V_3") (pintype "power_in"))
    )
    (net (code "53") (name "5V") (class "Default")
      (node (ref "F1") (pin "2") (pinfunction "2_2") (pintype "passive"))
      (node (ref "K60") (pin "124") (pinfunction "5V_124") (pintype "passive"))
      (node (ref "LED_5") (pin "1") (pinfunction "A_1") (pintype "passive"))
      (node (ref "POWER") (pin "4") (pinfunction "5V_4") (pintype "power_in"))
      (node (ref "omron_left") (pin "2") (pinfunction "5v_2") (pintype "power_in"))
      (node (ref "omron_right") (pin "2") (pinfunction "5v_2") (pintype "power_in"))
      (node (ref "paizu3") (pin "2") (pinfunction "2_2") (pintype "power_in"))
      (node (ref "paizu3") (pin "4") (pinfunction "4_4") (pintype "power_in"))
      (node (ref "paizu3") (pin "6") (pinfunction "6_6") (pintype "power_in"))
      (node (ref "paizu3") (pin "8") (pinfunction "8_8") (pintype "power_in"))
    )
    (net (code "54") (name "GND") (class "Default")
      (node (ref "BSS306N") (pin "1") (pinfunction "D_1") (pintype "passive"))
      (node (ref "BSS306N") (pin "3") (pinfunction "S_3") (pintype "passive"))
      (node (ref "C16") (pin "1") (pinfunction "1_1") (pintype "passive"))
      (node (ref "C18") (pin "1") (pinfunction "1_1") (pintype "passive"))
      (node (ref "C3") (pin "1") (pinfunction "1_1") (pintype "passive"))
      (node (ref "C31") (pin "1") (pinfunction "1_1") (pintype "passive"))
      (node (ref "C32") (pin "1") (pinfunction "1_1") (pintype "passive"))
      (node (ref "C4") (pin "2") (pinfunction "+_2") (pintype "passive"))
      (node (ref "C5") (pin "2") (pinfunction "2_2") (pintype "passive"))
      (node (ref "C6") (pin "2") (pinfunction "+_2") (pintype "passive"))
      (node (ref "C7") (pin "2") (pinfunction "2_2") (pintype "passive"))
      (node (ref "CA1") (pin "1") (pinfunction "1_1") (pintype "passive"))
      (node (ref "CB1") (pin "1") (pinfunction "1_1") (pintype "passive"))
      (node (ref "CB2") (pin "2") (pinfunction "2_2") (pintype "passive"))
      (node (ref "CC3") (pin "1") (pinfunction "1_1") (pintype "passive"))
      (node (ref "CD1") (pin "1") (pinfunction "1_1") (pintype "passive"))
      (node (ref "CD2") (pin "2") (pinfunction "2_2") (pintype "passive"))
      (node (ref "CE1") (pin "1") (pinfunction "1_1") (pintype "passive"))
      (node (ref "CF1") (pin "1") (pinfunction "1_1") (pintype "passive"))
      (node (ref "CF2") (pin "2") (pinfunction "2_2") (pintype "passive"))
      (node (ref "CON1") (pin "1") (pinfunction "1_1") (pintype "passive"))
      (node (ref "K60") (pin "123") (pinfunction "GND_123") (pintype "passive"))
      (node (ref "L6932-1") (pin "5") (pinfunction "GND_5") (pintype "power_in"))
      (node (ref "L6932-1") (pin "6") (pinfunction "GND_6") (pintype "power_in"))
      (node (ref "L6932-1") (pin "7") (pinfunction "GND_7") (pintype "power_in"))
      (node (ref "L6932-1") (pin "8") (pinfunction "GND_8") (pintype "power_in"))
      (node (ref "L6932-2") (pin "5") (pinfunction "GND_5") (pintype "power_in"))
      (node (ref "L6932-2") (pin "6") (pinfunction "GND_6") (pintype "power_in"))
      (node (ref "L6932-2") (pin "7") (pinfunction "GND_7") (pintype "power_in"))
      (node (ref "L6932-2") (pin "8") (pinfunction "GND_8") (pintype "power_in"))
      (node (ref "LM1117-5") (pin "1") (pinfunction "GND_1") (pintype "power_in"))
      (node (ref "POWER") (pin "1") (pinfunction "GND_1") (pintype "power_in"))
      (node (ref "POWER") (pin "2") (pinfunction "GND_2") (pintype "power_in"))
      (node (ref "R1") (pin "1") (pinfunction "1_1") (pintype "passive"))
      (node (ref "R10k_7") (pin "1") (pinfunction "1_1") (pintype "passive"))
      (node (ref "R10k_8") (pin "1") (pinfunction "1_1") (pintype "passive"))
      (node (ref "R2") (pin "1") (pinfunction "1_1") (pintype "passive"))
      (node (ref "R60") (pin "1") (pinfunction "1_1") (pintype "passive"))
      (node (ref "RA2") (pin "1") (pinfunction "1_1") (pintype "passive"))
      (node (ref "RB2") (pin "1") (pinfunction "1_1") (pintype "passive"))
      (node (ref "RC2") (pin "1") (pinfunction "1_1") (pintype "passive"))
      (node (ref "RD2") (pin "1") (pinfunction "1_1") (pintype "passive"))
      (node (ref "RE2") (pin "1") (pinfunction "1_1") (pintype "passive"))
      (node (ref "RF2") (pin "1") (pinfunction "1_1") (pintype "passive"))
      (node (ref "TLV2462_1") (pin "4") (pinfunction "GND_4") (pintype "power_in"))
      (node (ref "TLV2462_2") (pin "4") (pinfunction "GND_4") (pintype "power_in"))
      (node (ref "TLV2462_3") (pin "4") (pinfunction "GND_4") (pintype "power_in"))
      (node (ref "bluetooth") (pin "2") (pinfunction "GND_2") (pintype "power_in"))
      (node (ref "boma1") (pin "10") (pinfunction "10_10") (pintype "power_in"))
      (node (ref "boma1") (pin "12") (pinfunction "12_12") (pintype "power_in"))
      (node (ref "boma1") (pin "14") (pinfunction "14_14") (pintype "power_in"))
      (node (ref "boma1") (pin "16") (pinfunction "16_16") (pintype "power_in"))
      (node (ref "boma1") (pin "2") (pinfunction "2_2") (pintype "power_in"))
      (node (ref "boma1") (pin "4") (pinfunction "4_4") (pintype "power_in"))
      (node (ref "boma1") (pin "6") (pinfunction "6_6") (pintype "power_in"))
      (node (ref "boma1") (pin "8") (pinfunction "8_8") (pintype "power_in"))
      (node (ref "button1") (pin "2") (pinfunction "2_2") (pintype "passive"))
      (node (ref "button2") (pin "2") (pinfunction "2_2") (pintype "passive"))
      (node (ref "button3") (pin "2") (pinfunction "2_2") (pintype "passive"))
      (node (ref "button4") (pin "2") (pinfunction "2_2") (pintype "passive"))
      (node (ref "button5") (pin "2") (pinfunction "2_2") (pintype "passive"))
      (node (ref "button6") (pin "2") (pinfunction "2_2") (pintype "passive"))
      (node (ref "dianci") (pin "1") (pinfunction "GND_1") (pintype "power_in"))
      (node (ref "interface_sdcard") (pin "1") (pinfunction "GND_1") (pintype "power_in"))
      (node (ref "oled") (pin "1") (pinfunction "GND_1") (pintype "passive"))
      (node (ref "omron_left") (pin "1") (pinfunction "GND_1") (pintype "power_in"))
      (node (ref "omron_right") (pin "1") (pinfunction "GND_1") (pintype "power_in"))
      (node (ref "paizu2") (pin "2") (pinfunction "2_2") (pintype "power_in"))
      (node (ref "paizu2") (pin "4") (pinfunction "4_4") (pintype "power_in"))
      (node (ref "paizu2") (pin "6") (pinfunction "6_6") (pintype "power_in"))
      (node (ref "paizu2") (pin "8") (pinfunction "8_8") (pintype "power_in"))
      (node (ref "pwm") (pin "1") (pinfunction "GND_1") (pintype "power_in"))
      (node (ref "sdcard") (pin "6") (pinfunction "VSS_6") (pintype "power_in"))
      (node (ref "sdcard") (pin "G1") (pinfunction "G1_G1") (pintype "power_in"))
      (node (ref "sdcard") (pin "G2") (pinfunction "G2_G2") (pintype "power_in"))
      (node (ref "sdcard") (pin "G3") (pinfunction "G3_G3") (pintype "power_in"))
      (node (ref "sdcard") (pin "G4") (pinfunction "G4_G4") (pintype "power_in"))
      (node (ref "tuoluoyi") (pin "4") (pinfunction "GND_4") (pintype "passive"))
    )
    (net (code "55") (name "Net-(BSS306N-G)") (class "Default")
      (node (ref "BSS306N") (pin "2") (pinfunction "G_2") (pintype "passive"))
      (node (ref "C16") (pin "2") (pinfunction "2_2") (pintype "passive"))
      (node (ref "C4") (pin "1") (pinfunction "-_1") (pintype "passive"))
      (node (ref "C5") (pin "1") (pinfunction "1_1") (pintype "passive"))
      (node (ref "CON1") (pin "2") (pinfunction "2_2") (pintype "passive"))
      (node (ref "L6932-1") (pin "1") (pinfunction "EN_1") (pintype "power_in"))
      (node (ref "L6932-1") (pin "2") (pinfunction "IN_2") (pintype "power_in"))
      (node (ref "L6932-2") (pin "1") (pinfunction "EN_1") (pintype "power_in"))
      (node (ref "L6932-2") (pin "2") (pinfunction "IN_2") (pintype "power_in"))
      (node (ref "LM1117-5") (pin "3") (pinfunction "VIN_3") (pintype "power_in"))
    )
    (net (code "56") (name "Net-(C6--)") (class "Default")
      (node (ref "C6") (pin "1") (pinfunction "-_1") (pintype "passive"))
      (node (ref "C7") (pin "1") (pinfunction "1_1") (pintype "passive"))
      (node (ref "F1") (pin "1") (pinfunction "1_1") (pintype "passive"))
      (node (ref "LM1117-5") (pin "2") (pinfunction "VOUT_2") (pintype "power_in"))
    )
    (net (code "57") (name "Net-(L6932-1-ADJ)") (class "Default")
      (node (ref "C2") (pin "1") (pinfunction "1_1") (pintype "passive"))
      (node (ref "L6932-1") (pin "3") (pinfunction "ADJ_3") (pintype "power_in"))
      (node (ref "R10k_7") (pin "2") (pinfunction "2_2") (pintype "passive"))
      (node (ref "R15") (pin "1") (pinfunction "1_1") (pintype "passive"))
    )
    (net (code "58") (name "Net-(L6932-2-ADJ)") (class "Default")
      (node (ref "C30") (pin "1") (pinfunction "1_1") (pintype "passive"))
      (node (ref "L6932-2") (pin "3") (pinfunction "ADJ_3") (pintype "power_in"))
      (node (ref "R10k_8") (pin "2") (pinfunction "2_2") (pintype "passive"))
      (node (ref "R61") (pin "1") (pinfunction "1_1") (pintype "passive"))
    )
    (net (code "59") (name "Net-(LED_3.3_1-K)") (class "Default")
      (node (ref "LED_3.3_1") (pin "2") (pinfunction "K_2") (pintype "passive"))
      (node (ref "R60") (pin "2") (pinfunction "2_2") (pintype "passive"))
    )
    (net (code "60") (name "Net-(LED_3.3_2-K)") (class "Default")
      (node (ref "LED_3.3_2") (pin "2") (pinfunction "K_2") (pintype "passive"))
      (node (ref "R1") (pin "2") (pinfunction "2_2") (pintype "passive"))
    )
    (net (code "61") (name "Net-(LED_5-K)") (class "Default")
      (node (ref "LED_5") (pin "2") (pinfunction "K_2") (pintype "passive"))
      (node (ref "R2") (pin "2") (pinfunction "2_2") (pintype "passive"))
    )
    (net (code "62") (name "Net-(RA1-Pad2)") (class "Default")
      (node (ref "RA1") (pin "2") (pinfunction "2_2") (pintype "passive"))
      (node (ref "TLV2462_1") (pin "3") (pinfunction "3_3") (pintype "input"))
    )
    (net (code "63") (name "Net-(RA2-Pad2)") (class "Default")
      (node (ref "RA2") (pin "2") (pinfunction "2_2") (pintype "passive"))
      (node (ref "RA3") (pin "1") (pinfunction "1_1") (pintype "passive"))
      (node (ref "TLV2462_1") (pin "2") (pinfunction "2_2") (pintype "input"))
    )
    (net (code "64") (name "Net-(RB1-Pad2)") (class "Default")
      (node (ref "RB1") (pin "2") (pinfunction "2_2") (pintype "passive"))
      (node (ref "TLV2462_1") (pin "5") (pinfunction "5_5") (pintype "input"))
    )
    (net (code "65") (name "Net-(RB2-Pad2)") (class "Default")
      (node (ref "RB2") (pin "2") (pinfunction "2_2") (pintype "passive"))
      (node (ref "RB3") (pin "1") (pinfunction "1_1") (pintype "passive"))
      (node (ref "TLV2462_1") (pin "6") (pinfunction "6_6") (pintype "input"))
    )
    (net (code "66") (name "Net-(RC1-Pad2)") (class "Default")
      (node (ref "RC1") (pin "2") (pinfunction "2_2") (pintype "passive"))
      (node (ref "TLV2462_2") (pin "3") (pinfunction "3_3") (pintype "input"))
    )
    (net (code "67") (name "Net-(RC2-Pad2)") (class "Default")
      (node (ref "RC2") (pin "2") (pinfunction "2_2") (pintype "passive"))
      (node (ref "RC3") (pin "1") (pinfunction "1_1") (pintype "passive"))
      (node (ref "TLV2462_2") (pin "2") (pinfunction "2_2") (pintype "input"))
    )
    (net (code "68") (name "Net-(RD1-Pad2)") (class "Default")
      (node (ref "RD1") (pin "2") (pinfunction "2_2") (pintype "passive"))
      (node (ref "TLV2462_2") (pin "5") (pinfunction "5_5") (pintype "input"))
    )
    (net (code "69") (name "Net-(RD2-Pad2)") (class "Default")
      (node (ref "RD2") (pin "2") (pinfunction "2_2") (pintype "passive"))
      (node (ref "RD3") (pin "1") (pinfunction "1_1") (pintype "passive"))
      (node (ref "TLV2462_2") (pin "6") (pinfunction "6_6") (pintype "input"))
    )
    (net (code "70") (name "Net-(RE1-Pad2)") (class "Default")
      (node (ref "RE1") (pin "2") (pinfunction "2_2") (pintype "passive"))
      (node (ref "TLV2462_3") (pin "3") (pinfunction "3_3") (pintype "input"))
    )
    (net (code "71") (name "Net-(RE2-Pad2)") (class "Default")
      (node (ref "RE2") (pin "2") (pinfunction "2_2") (pintype "passive"))
      (node (ref "RE3") (pin "1") (pinfunction "1_1") (pintype "passive"))
      (node (ref "TLV2462_3") (pin "2") (pinfunction "2_2") (pintype "input"))
    )
    (net (code "72") (name "Net-(RE3-Pad2)") (class "Default")
      (node (ref "RE3") (pin "2") (pinfunction "2_2") (pintype "passive"))
      (node (ref "dianciR5") (pin "2") (pinfunction "2_2") (pintype "passive"))
    )
    (net (code "73") (name "Net-(RE4-Pad1)") (class "Default")
      (node (ref "RE4") (pin "1") (pinfunction "1_1") (pintype "passive"))
      (node (ref "TLV2462_3") (pin "1") (pinfunction "1_1") (pintype "output"))
      (node (ref "dianciR5") (pin "1") (pinfunction "1_1") (pintype "passive"))
      (node (ref "dianciR5") (pin "3") (pinfunction "3_3") (pintype "passive"))
    )
    (net (code "74") (name "Net-(RF1-Pad2)") (class "Default")
      (node (ref "RF1") (pin "2") (pinfunction "2_2") (pintype "passive"))
      (node (ref "TLV2462_3") (pin "5") (pinfunction "5_5") (pintype "input"))
    )
    (net (code "75") (name "Net-(RF2-Pad2)") (class "Default")
      (node (ref "RF2") (pin "2") (pinfunction "2_2") (pintype "passive"))
      (node (ref "RF3") (pin "1") (pinfunction "1_1") (pintype "passive"))
      (node (ref "TLV2462_3") (pin "6") (pinfunction "6_6") (pintype "input"))
    )
    (net (code "76") (name "Net-(dianciR1-BOT)") (class "Default")
      (node (ref "RA3") (pin "2") (pinfunction "2_2") (pintype "passive"))
      (node (ref "dianciR1") (pin "2") (pinfunction "BOT_2") (pintype "passive"))
    )
    (net (code "77") (name "Net-(dianciR1-TAP)") (class "Default")
      (node (ref "RA4") (pin "1") (pinfunction "1_1") (pintype "passive"))
      (node (ref "TLV2462_1") (pin "1") (pinfunction "1_1") (pintype "output"))
      (node (ref "dianciR1") (pin "1") (pinfunction "TOP_1") (pintype "passive"))
      (node (ref "dianciR1") (pin "3") (pinfunction "TAP_3") (pintype "passive"))
    )
    (net (code "78") (name "Net-(dianciR2-BOT)") (class "Default")
      (node (ref "RB3") (pin "2") (pinfunction "2_2") (pintype "passive"))
      (node (ref "dianciR2") (pin "2") (pinfunction "BOT_2") (pintype "passive"))
    )
    (net (code "79") (name "Net-(dianciR2-TAP)") (class "Default")
      (node (ref "RB4") (pin "1") (pinfunction "1_1") (pintype "passive"))
      (node (ref "TLV2462_1") (pin "7") (pinfunction "7_7") (pintype "output"))
      (node (ref "dianciR2") (pin "1") (pinfunction "TOP_1") (pintype "passive"))
      (node (ref "dianciR2") (pin "3") (pinfunction "TAP_3") (pintype "passive"))
    )
    (net (code "80") (name "Net-(dianciR3-BOT)") (class "Default")
      (node (ref "RC3") (pin "2") (pinfunction "2_2") (pintype "passive"))
      (node (ref "dianciR3") (pin "2") (pinfunction "BOT_2") (pintype "passive"))
    )
    (net (code "81") (name "Net-(dianciR3-TAP)") (class "Default")
      (node (ref "RC4") (pin "1") (pinfunction "1_1") (pintype "passive"))
      (node (ref "TLV2462_2") (pin "1") (pinfunction "1_1") (pintype "output"))
      (node (ref "dianciR3") (pin "1") (pinfunction "TOP_1") (pintype "passive"))
      (node (ref "dianciR3") (pin "3") (pinfunction "TAP_3") (pintype "passive"))
    )
    (net (code "82") (name "Net-(dianciR4-BOT)") (class "Default")
      (node (ref "RD3") (pin "2") (pinfunction "2_2") (pintype "passive"))
      (node (ref "dianciR4") (pin "2") (pinfunction "BOT_2") (pintype "passive"))
    )
    (net (code "83") (name "Net-(dianciR4-TAP)") (class "Default")
      (node (ref "RD4") (pin "1") (pinfunction "1_1") (pintype "passive"))
      (node (ref "TLV2462_2") (pin "7") (pinfunction "7_7") (pintype "output"))
      (node (ref "dianciR4") (pin "1") (pinfunction "TOP_1") (pintype "passive"))
      (node (ref "dianciR4") (pin "3") (pinfunction "TAP_3") (pintype "passive"))
    )
    (net (code "84") (name "Net-(dianciR6-BOT)") (class "Default")
      (node (ref "RF3") (pin "2") (pinfunction "2_2") (pintype "passive"))
      (node (ref "dianciR6") (pin "2") (pinfunction "BOT_2") (pintype "passive"))
    )
    (net (code "85") (name "Net-(dianciR6-TAP)") (class "Default")
      (node (ref "RF4") (pin "1") (pinfunction "1_1") (pintype "passive"))
      (node (ref "TLV2462_3") (pin "7") (pinfunction "7_7") (pintype "output"))
      (node (ref "dianciR6") (pin "1") (pinfunction "TOP_1") (pintype "passive"))
      (node (ref "dianciR6") (pin "3") (pinfunction "TAP_3") (pintype "passive"))
    )
    (net (code "86") (name "unconnected-(CB2-Pad1)") (class "Default")
      (node (ref "CB2") (pin "1") (pinfunction "1_1") (pintype "passive"))
    )
    (net (code "87") (name "unconnected-(CD2-Pad1)") (class "Default")
      (node (ref "CD2") (pin "1") (pinfunction "1_1") (pintype "passive"))
    )
    (net (code "88") (name "unconnected-(CF2-Pad1)") (class "Default")
      (node (ref "CF2") (pin "1") (pinfunction "1_1") (pintype "passive"))
    )
    (net (code "89") (name "unconnected-(K60-ADC0_SE16-Pad322)") (class "Default")
      (node (ref "K60") (pin "322") (pinfunction "ADC0_SE16_322") (pintype "passive"))
    )
    (net (code "90") (name "unconnected-(K60-ADC1_SE16-Pad321)") (class "Default")
      (node (ref "K60") (pin "321") (pinfunction "ADC1_SE16_321") (pintype "passive"))
    )
    (net (code "91") (name "unconnected-(K60-DAC0-Pad320)") (class "Default")
      (node (ref "K60") (pin "320") (pinfunction "DAC0_320") (pintype "passive"))
    )
    (net (code "92") (name "unconnected-(K60-DAC1-Pad319)") (class "Default")
      (node (ref "K60") (pin "319") (pinfunction "DAC1_319") (pintype "passive"))
    )
    (net (code "93") (name "unconnected-(K60-NC-Pad323)") (class "Default")
      (node (ref "K60") (pin "323") (pinfunction "NC_323") (pintype "passive"))
    )
    (net (code "94") (name "unconnected-(K60-NC-Pad324)") (class "Default")
      (node (ref "K60") (pin "324") (pinfunction "NC_324") (pintype "passive"))
    )
    (net (code "95") (name "unconnected-(K60-PGA0_DM-Pad229)") (class "Default")
      (node (ref "K60") (pin "229") (pinfunction "PGA0_DM_229") (pintype "passive"))
    )
    (net (code "96") (name "unconnected-(K60-PGA0_DP-Pad230)") (class "Default")
      (node (ref "K60") (pin "230") (pinfunction "PGA0_DP_230") (pintype "passive"))
    )
    (net (code "97") (name "unconnected-(K60-PGA1_DM-Pad231)") (class "Default")
      (node (ref "K60") (pin "231") (pinfunction "PGA1_DM_231") (pintype "passive"))
    )
    (net (code "98") (name "unconnected-(K60-PGA1_DP-Pad232)") (class "Default")
      (node (ref "K60") (pin "232") (pinfunction "PGA1_DP_232") (pintype "passive"))
    )
    (net (code "99") (name "unconnected-(K60-PGA2_DM-Pad225)") (class "Default")
      (node (ref "K60") (pin "225") (pinfunction "PGA2_DM_225") (pintype "passive"))
    )
    (net (code "100") (name "unconnected-(K60-PGA2_DP-Pad226)") (class "Default")
      (node (ref "K60") (pin "226") (pinfunction "PGA2_DP_226") (pintype "passive"))
    )
    (net (code "101") (name "unconnected-(K60-PGA3_DM-Pad227)") (class "Default")
      (node (ref "K60") (pin "227") (pinfunction "PGA3_DM_227") (pintype "passive"))
    )
    (net (code "102") (name "unconnected-(K60-PGA3_DP-Pad228)") (class "Default")
      (node (ref "K60") (pin "228") (pinfunction "PGA3_DP_228") (pintype "passive"))
    )
    (net (code "103") (name "unconnected-(K60-PTA5-Pad313)") (class "Default")
      (node (ref "K60") (pin "313") (pinfunction "PTA5_313") (pintype "passive"))
    )
    (net (code "104") (name "unconnected-(K60-PTA6-Pad312)") (class "Default")
      (node (ref "K60") (pin "312") (pinfunction "PTA6_312") (pintype "passive"))
    )
    (net (code "105") (name "unconnected-(K60-PTA7-Pad311)") (class "Default")
      (node (ref "K60") (pin "311") (pinfunction "PTA7_311") (pintype "passive"))
    )
    (net (code "106") (name "unconnected-(K60-PTA8-Pad310)") (class "Default")
      (node (ref "K60") (pin "310") (pinfunction "PTA8_310") (pintype "passive"))
    )
    (net (code "107") (name "unconnected-(K60-PTA9-Pad309)") (class "Default")
      (node (ref "K60") (pin "309") (pinfunction "PTA9_309") (pintype "passive"))
    )
    (net (code "108") (name "unconnected-(K60-PTA16-Pad302)") (class "Default")
      (node (ref "K60") (pin "302") (pinfunction "PTA16_302") (pintype "passive"))
    )
    (net (code "109") (name "unconnected-(K60-PTA17-Pad301)") (class "Default")
      (node (ref "K60") (pin "301") (pinfunction "PTA17_301") (pintype "passive"))
    )
    (net (code "110") (name "unconnected-(K60-PTA19-Pad431)") (class "Default")
      (node (ref "K60") (pin "431") (pinfunction "PTA19_431") (pintype "passive"))
    )
    (net (code "111") (name "unconnected-(K60-PTA24-Pad429)") (class "Default")
      (node (ref "K60") (pin "429") (pinfunction "PTA24_429") (pintype "passive"))
    )
    (net (code "112") (name "unconnected-(K60-PTA25-Pad432)") (class "Default")
      (node (ref "K60") (pin "432") (pinfunction "PTA25_432") (pintype "passive"))
    )
    (net (code "113") (name "unconnected-(K60-PTA26-Pad428)") (class "Default")
      (node (ref "K60") (pin "428") (pinfunction "PTA26_428") (pintype "passive"))
    )
    (net (code "114") (name "unconnected-(K60-PTA27-Pad430)") (class "Default")
      (node (ref "K60") (pin "430") (pinfunction "PTA27_430") (pintype "passive"))
    )
    (net (code "115") (name "unconnected-(K60-PTA28-Pad427)") (class "Default")
      (node (ref "K60") (pin "427") (pinfunction "PTA28_427") (pintype "passive"))
    )
    (net (code "116") (name "unconnected-(K60-PTA29-Pad426)") (class "Default")
      (node (ref "K60") (pin "426") (pinfunction "PTA29_426") (pintype "passive"))
    )
    (net (code "117") (name "unconnected-(K60-PTB0-Pad424)") (class "Default")
      (node (ref "K60") (pin "424") (pinfunction "PTB0_424") (pintype "passive"))
    )
    (net (code "118") (name "unconnected-(K60-PTB2-Pad422)") (class "Default")
      (node (ref "K60") (pin "422") (pinfunction "PTB2_422") (pintype "passive"))
    )
    (net (code "119") (name "unconnected-(K60-PTB3-Pad423)") (class "Default")
      (node (ref "K60") (pin "423") (pinfunction "PTB3_423") (pintype "passive"))
    )
    (net (code "120") (name "unconnected-(K60-PTB8-Pad417)") (class "Default")
      (node (ref "K60") (pin "417") (pinfunction "PTB8_417") (pintype "passive"))
    )
    (net (code "121") (name "unconnected-(K60-PTB9-Pad416)") (class "Default")
      (node (ref "K60") (pin "416") (pinfunction "PTB9_416") (pintype "passive"))
    )
    (net (code "122") (name "unconnected-(K60-PTB11-Pad415)") (class "Default")
      (node (ref "K60") (pin "415") (pinfunction "PTB11_415") (pintype "passive"))
    )
    (net (code "123") (name "unconnected-(K60-PTB16-Pad412)") (class "Default")
      (node (ref "K60") (pin "412") (pinfunction "PTB16_412") (pintype "passive"))
    )
    (net (code "124") (name "unconnected-(K60-PTB17-Pad413)") (class "Default")
      (node (ref "K60") (pin "413") (pinfunction "PTB17_413") (pintype "passive"))
    )
    (net (code "125") (name "unconnected-(K60-PTB18-Pad410)") (class "Default")
      (node (ref "K60") (pin "410") (pinfunction "PTB18_410") (pintype "passive"))
    )
    (net (code "126") (name "unconnected-(K60-PTB19-Pad411)") (class "Default")
      (node (ref "K60") (pin "411") (pinfunction "PTB19_411") (pintype "passive"))
    )
    (net (code "127") (name "unconnected-(K60-PTB20-Pad408)") (class "Default")
      (node (ref "K60") (pin "408") (pinfunction "PTB20_408") (pintype "passive"))
    )
    (net (code "128") (name "unconnected-(K60-PTB21-Pad409)") (class "Default")
      (node (ref "K60") (pin "409") (pinfunction "PTB21_409") (pintype "passive"))
    )
    (net (code "129") (name "unconnected-(K60-PTB22-Pad406)") (class "Default")
      (node (ref "K60") (pin "406") (pinfunction "PTB22_406") (pintype "passive"))
    )
    (net (code "130") (name "unconnected-(K60-PTB23-Pad407)") (class "Default")
      (node (ref "K60") (pin "407") (pinfunction "PTB23_407") (pintype "passive"))
    )
    (net (code "131") (name "unconnected-(K60-PTC0-Pad405)") (class "Default")
      (node (ref "K60") (pin "405") (pinfunction "PTC0_405") (pintype "passive"))
    )
    (net (code "132") (name "unconnected-(K60-PTC3-Pad403)") (class "Default")
      (node (ref "K60") (pin "403") (pinfunction "PTC3_403") (pintype "passive"))
    )
    (net (code "133") (name "unconnected-(K60-PTD0-Pad115)") (class "Default")
      (node (ref "K60") (pin "115") (pinfunction "PTD0_115") (pintype "passive"))
    )
    (net (code "134") (name "unconnected-(K60-PTD1-Pad117)") (class "Default")
      (node (ref "K60") (pin "117") (pinfunction "PTD1_117") (pintype "passive"))
    )
    (net (code "135") (name "unconnected-(K60-PTD2-Pad118)") (class "Default")
      (node (ref "K60") (pin "118") (pinfunction "PTD2_118") (pintype "passive"))
    )
    (net (code "136") (name "unconnected-(K60-PTD3-Pad119)") (class "Default")
      (node (ref "K60") (pin "119") (pinfunction "PTD3_119") (pintype "passive"))
    )
    (net (code "137") (name "unconnected-(K60-PTD6-Pad122)") (class "Default")
      (node (ref "K60") (pin "122") (pinfunction "PTD6_122") (pintype "passive"))
    )
    (net (code "138") (name "unconnected-(K60-PTD7-Pad202)") (class "Default")
      (node (ref "K60") (pin "202") (pinfunction "PTD7_202") (pintype "passive"))
    )
    (net (code "139") (name "unconnected-(K60-PTD8-Pad204)") (class "Default")
      (node (ref "K60") (pin "204") (pinfunction "PTD8_204") (pintype "passive"))
    )
    (net (code "140") (name "unconnected-(K60-PTD9-Pad201)") (class "Default")
      (node (ref "K60") (pin "201") (pinfunction "PTD9_201") (pintype "passive"))
    )
    (net (code "141") (name "unconnected-(K60-PTD10-Pad203)") (class "Default")
      (node (ref "K60") (pin "203") (pinfunction "PTD10_203") (pintype "passive"))
    )
    (net (code "142") (name "unconnected-(K60-PTD11-Pad205)") (class "Default")
      (node (ref "K60") (pin "205") (pinfunction "PTD11_205") (pintype "passive"))
    )
    (net (code "143") (name "unconnected-(K60-PTD12-Pad206)") (class "Default")
      (node (ref "K60") (pin "206") (pinfunction "PTD12_206") (pintype "passive"))
    )
    (net (code "144") (name "unconnected-(K60-PTD13-Pad207)") (class "Default")
      (node (ref "K60") (pin "207") (pinfunction "PTD13_207") (pintype "passive"))
    )
    (net (code "145") (name "unconnected-(K60-PTD14-Pad208)") (class "Default")
      (node (ref "K60") (pin "208") (pinfunction "PTD14_208") (pintype "passive"))
    )
    (net (code "146") (name "unconnected-(K60-PTD15-Pad209)") (class "Default")
      (node (ref "K60") (pin "209") (pinfunction "PTD15_209") (pintype "passive"))
    )
    (net (code "147") (name "unconnected-(K60-PTE11-Pad220)") (class "Default")
      (node (ref "K60") (pin "220") (pinfunction "PTE11_220") (pintype "passive"))
    )
    (net (code "148") (name "unconnected-(K60-PTE12-Pad222)") (class "Default")
      (node (ref "K60") (pin "222") (pinfunction "PTE12_222") (pintype "passive"))
    )
    (net (code "149") (name "unconnected-(K60-PTE25-Pad317)") (class "Default")
      (node (ref "K60") (pin "317") (pinfunction "PTE25_317") (pintype "passive"))
    )
    (net (code "150") (name "unconnected-(K60-PTE26-Pad316)") (class "Default")
      (node (ref "K60") (pin "316") (pinfunction "PTE26_316") (pintype "passive"))
    )
    (net (code "151") (name "unconnected-(K60-PTE27-Pad315)") (class "Default")
      (node (ref "K60") (pin "315") (pinfunction "PTE27_315") (pintype "passive"))
    )
    (net (code "152") (name "unconnected-(K60-PTE28-Pad314)") (class "Default")
      (node (ref "K60") (pin "314") (pinfunction "PTE28_314") (pintype "passive"))
    )
    (net (code "153") (name "unconnected-(K60-USB0_DM-Pad223)") (class "Default")
      (node (ref "K60") (pin "223") (pinfunction "USB0_DM_223") (pintype "passive"))
    )
    (net (code "154") (name "unconnected-(K60-USB0_DP-Pad224)") (class "Default")
      (node (ref "K60") (pin "224") (pinfunction "USB0_DP_224") (pintype "passive"))
    )
    (net (code "155") (name "unconnected-(sdcard-CDN-Pad9)") (class "Default")
      (node (ref "sdcard") (pin "9") (pinfunction "CDN_9") (pintype "power_in"))
    )
    (net (code "156") (name "unconnected-(sdcard-DATA1-Pad8)") (class "Default")
      (node (ref "sdcard") (pin "8") (pinfunction "DATA1_8") (pintype "power_in"))
    )
    (net (code "157") (name "unconnected-(sdcard-DATA2-Pad1)") (class "Default")
      (node (ref "sdcard") (pin "1") (pinfunction "DATA2_1") (pintype "power_in"))
    )
  )
)
